# 16_PM8916_SMPS.net
KiCad netlist of a schematic drawn in Altium Designer
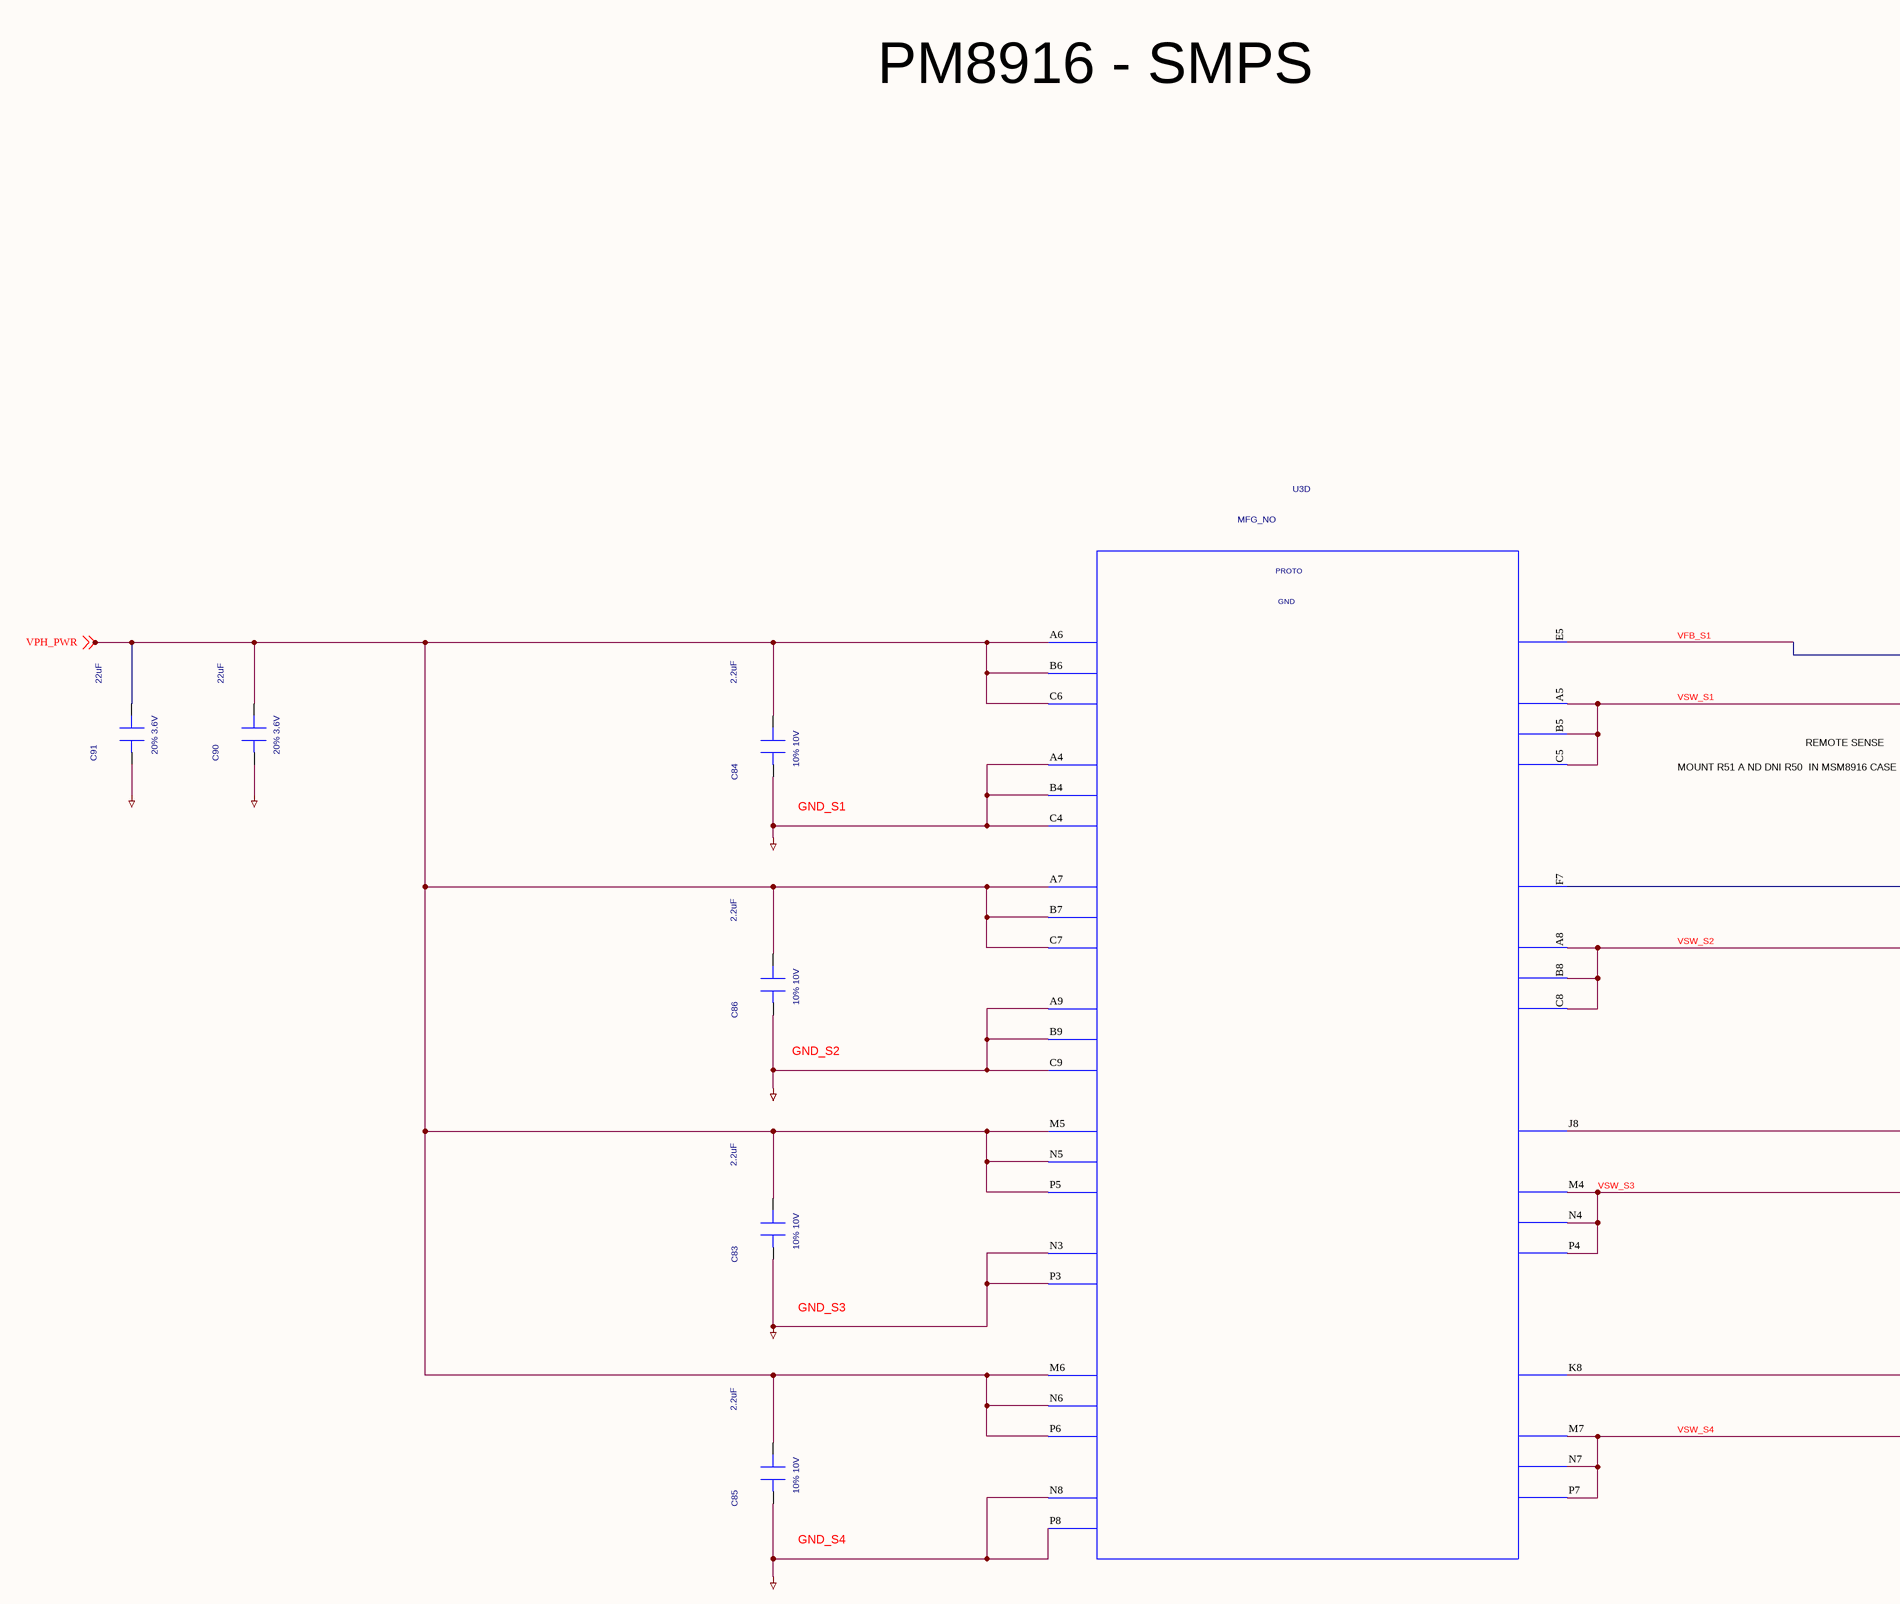
[diagram p0: 16 PM8916_SMPS.SchDoc, top left]
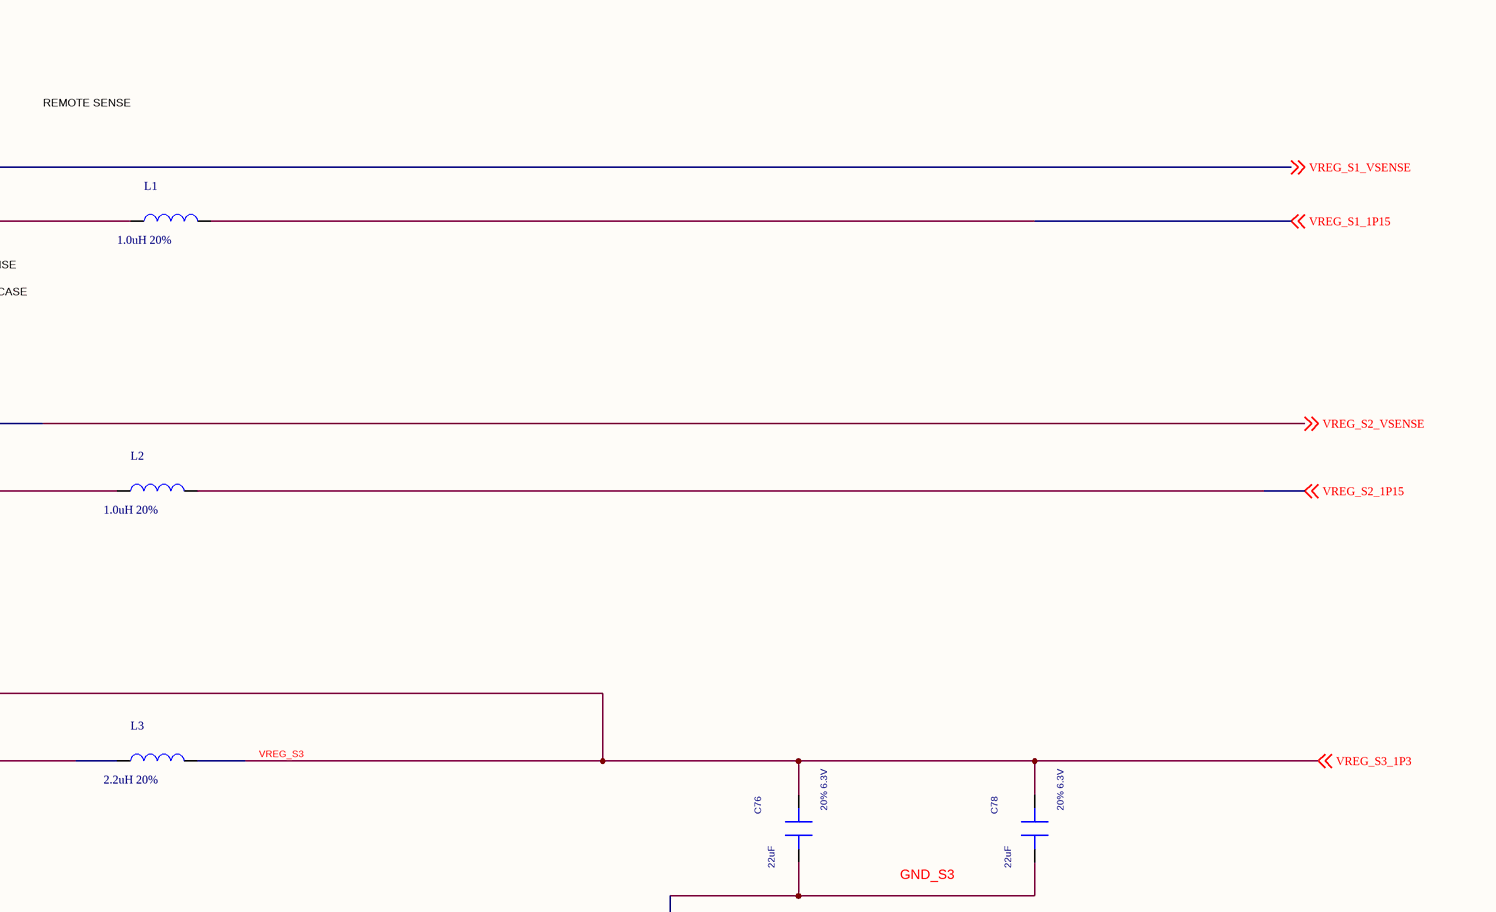
[diagram p1: 16 PM8916_SMPS.SchDoc, top right]
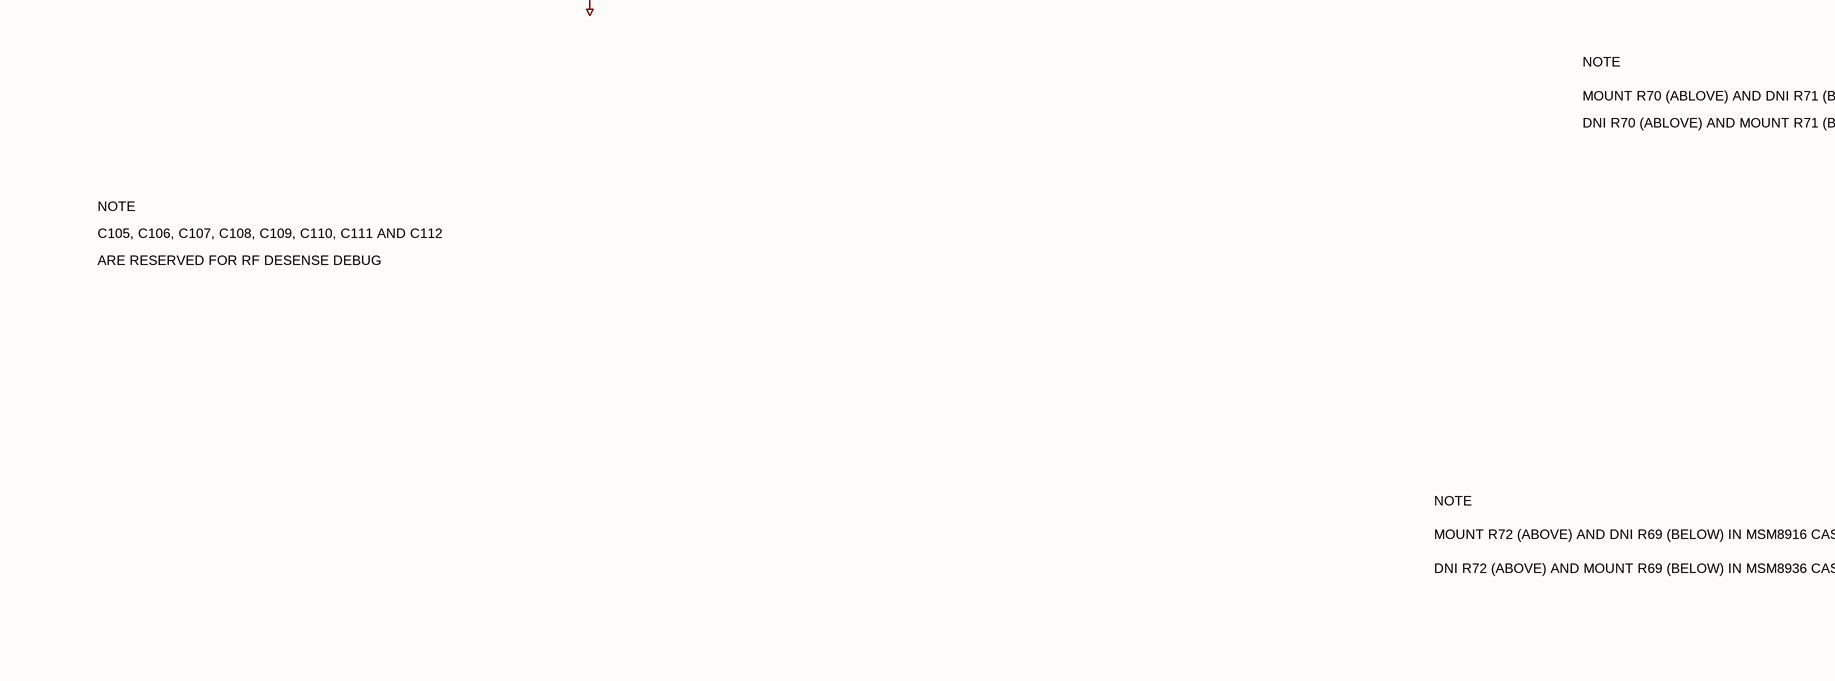
[diagram p2: 16 PM8916_SMPS.SchDoc, bottom left]
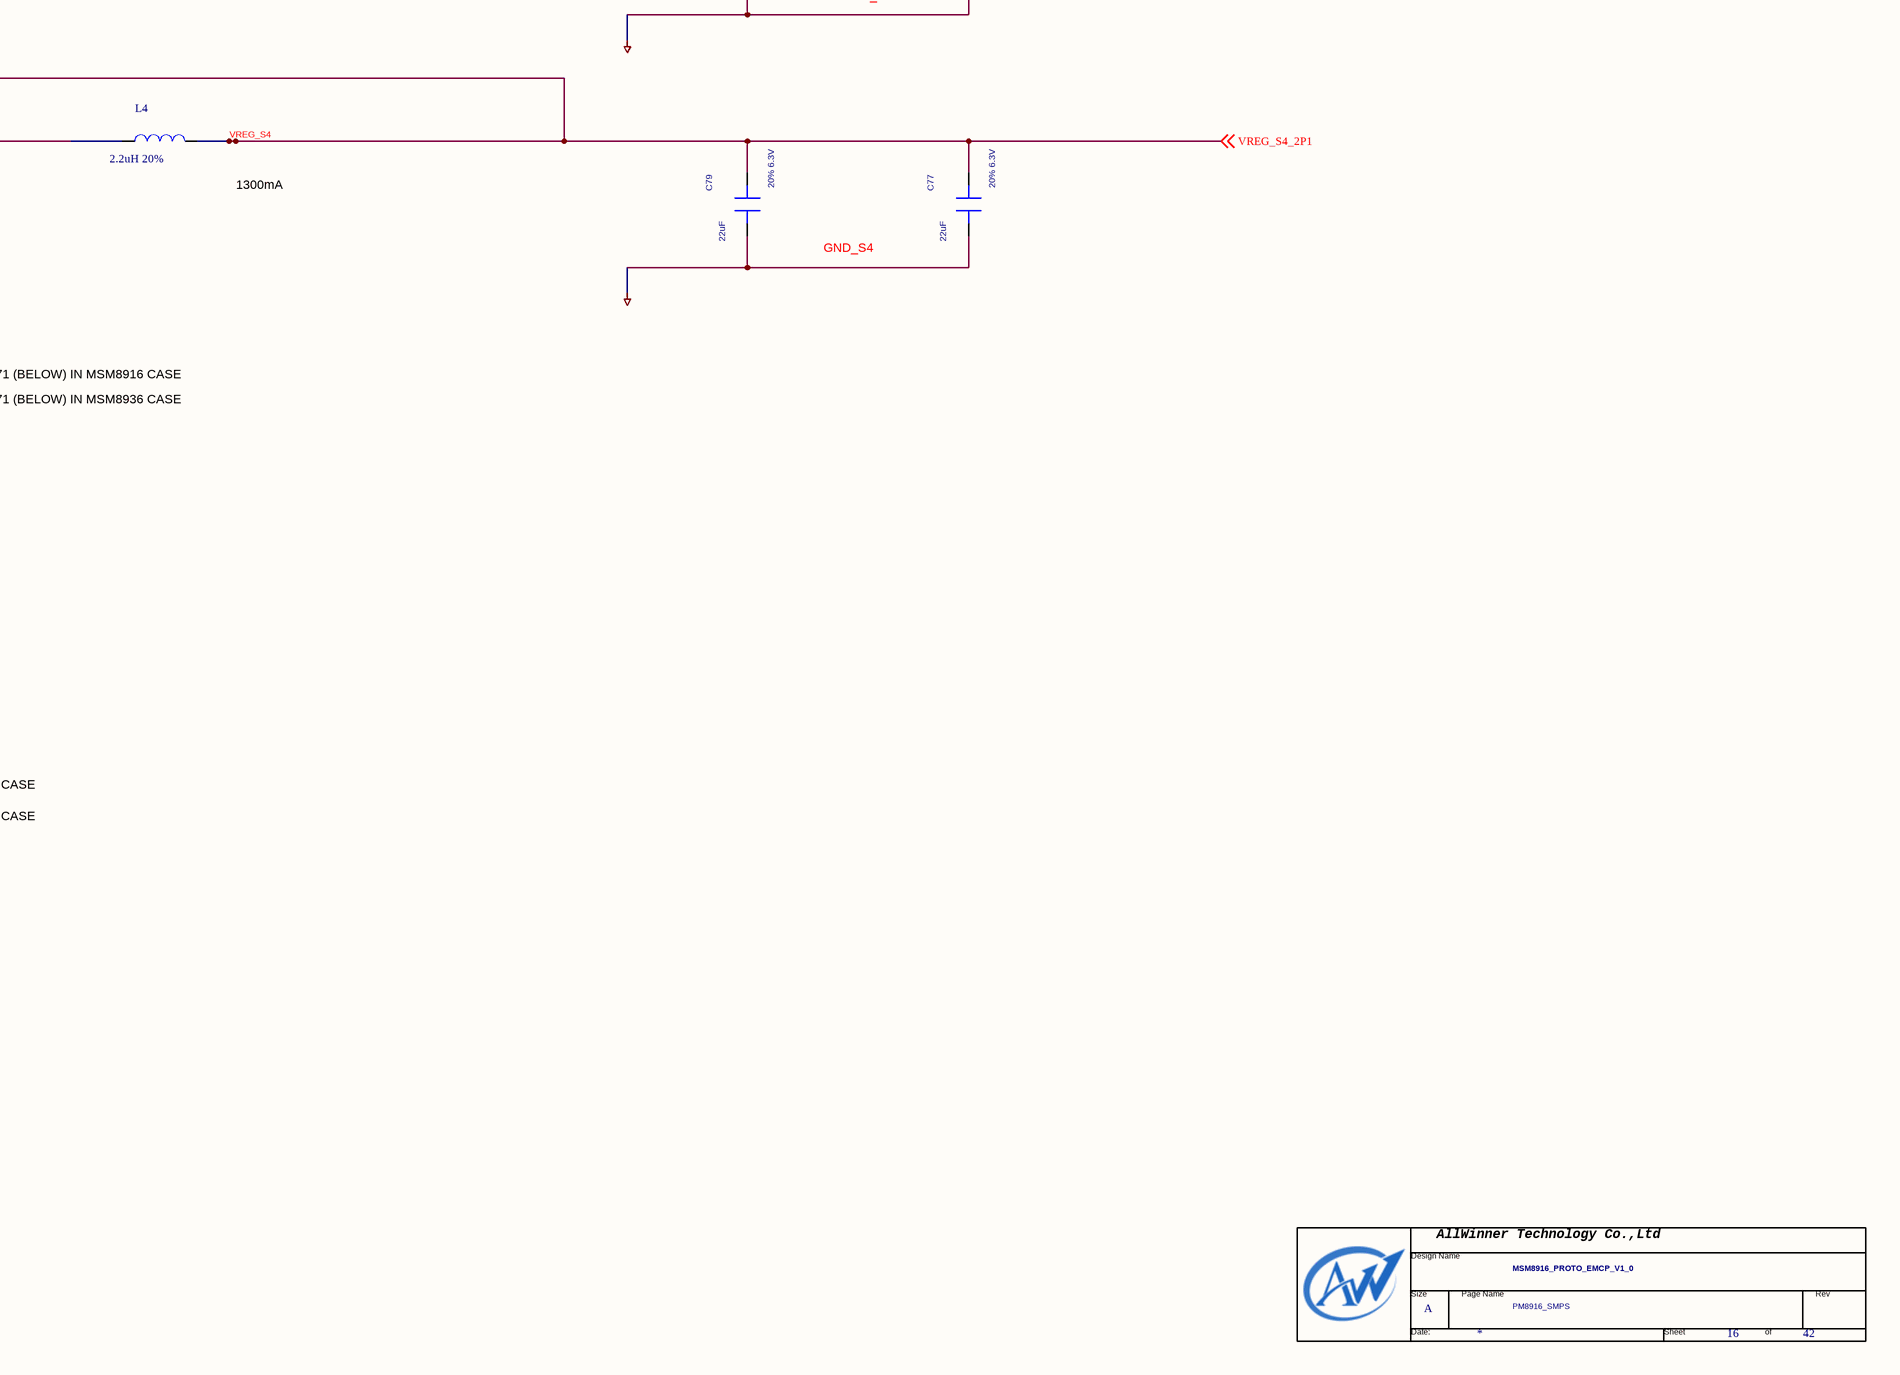
[diagram p3: 16 PM8916_SMPS.SchDoc, bottom right]

(export (version "E")
  (design (tool "Eeschema 10.0.6"))
  (components
    (comp (ref "C76")
      (value "22uF")
      (footprint "c0402")
      (fields (field (name "TOLERANCE") "20% 6.3V") (field (name "PART_NUMBER") "MCN_NO"))
      (libsource (lib "MSM8916_DRAM_PMIC_REF_Library") (part "CAP#1"))
    )
    (comp (ref "C77")
      (value "22uF")
      (footprint "c0402")
      (fields (field (name "TOLERANCE") "20% 6.3V") (field (name "PART_NUMBER") "MCN_NO"))
      (libsource (lib "MSM8916_DRAM_PMIC_REF_Library") (part "CAP#1"))
    )
    (comp (ref "C78")
      (value "22uF")
      (footprint "c0402")
      (fields (field (name "TOLERANCE") "20% 6.3V") (field (name "PART_NUMBER") "MCN_NO"))
      (libsource (lib "MSM8916_DRAM_PMIC_REF_Library") (part "CAP#1"))
    )
    (comp (ref "C79")
      (value "22uF")
      (footprint "c0402")
      (fields (field (name "TOLERANCE") "20% 6.3V") (field (name "PART_NUMBER") "MCN_NO"))
      (libsource (lib "MSM8916_DRAM_PMIC_REF_Library") (part "CAP#1"))
    )
    (comp (ref "C83")
      (value "2.2uF")
      (footprint "c0402")
      (fields (field (name "TOLERANCE") "10% 10V") (field (name "PART_NUMBER") "MCN_NO"))
      (libsource (lib "MSM8916_DRAM_PMIC_REF_Library") (part "CAP#1"))
    )
    (comp (ref "C84")
      (value "2.2uF")
      (footprint "c0402")
      (fields (field (name "TOLERANCE") "10% 10V") (field (name "PART_NUMBER") "MCN_NO"))
      (libsource (lib "MSM8916_DRAM_PMIC_REF_Library") (part "CAP#1"))
    )
    (comp (ref "C85")
      (value "2.2uF")
      (footprint "c0402")
      (fields (field (name "TOLERANCE") "10% 10V") (field (name "PART_NUMBER") "MCN_NO"))
      (libsource (lib "MSM8916_DRAM_PMIC_REF_Library") (part "CAP#1"))
    )
    (comp (ref "C86")
      (value "2.2uF")
      (footprint "c0402")
      (fields (field (name "TOLERANCE") "10% 10V") (field (name "PART_NUMBER") "MCN_NO"))
      (libsource (lib "MSM8916_DRAM_PMIC_REF_Library") (part "CAP#1"))
    )
    (comp (ref "C90")
      (value "22uF")
      (footprint "c0402")
      (fields (field (name "TOLERANCE") "20% 3.6V") (field (name "PART_NUMBER") "MCN_NO"))
      (libsource (lib "MSM8916_DRAM_PMIC_REF_Library") (part "CAP#1"))
    )
    (comp (ref "C91")
      (value "22uF")
      (footprint "c0402")
      (fields (field (name "TOLERANCE") "20% 3.6V") (field (name "PART_NUMBER") "MCN_NO"))
      (libsource (lib "MSM8916_DRAM_PMIC_REF_Library") (part "CAP#1"))
    )
    (comp (ref "L1")
      (value "1.0uH 20%")
      (footprint "c0402")
      (libsource (lib "MSM8916_DRAM_PMIC_REF_Library") (part "INDUCTOR_0"))
    )
    (comp (ref "L2")
      (value "1.0uH 20%")
      (footprint "c0402")
      (libsource (lib "MSM8916_DRAM_PMIC_REF_Library") (part "INDUCTOR_0"))
    )
    (comp (ref "L3")
      (value "2.2uH 20%")
      (footprint "c0402")
      (libsource (lib "MSM8916_DRAM_PMIC_REF_Library") (part "INDUCTOR_0"))
    )
    (comp (ref "L4")
      (value "2.2uH 20%")
      (footprint "c0402")
      (libsource (lib "MSM8916_DRAM_PMIC_REF_Library") (part "INDUCTOR_0"))
    )
    (comp (ref "U3")
      (value "ASIC_PM8916")
      (footprint "PM-8916-0-176NSP-TR-00-0")
      (fields
        (field (name "SYMNAME") "GND")
        (field (name "PART_NUMBER") "MCN_NO")
        (field (name "PART_ID") "MFG_NO")
        (field (name "BLOCKID") "PROTO")
      )
      (libsource (lib "MSM8916_DRAM_PMIC_REF_Library") (part "ASIC_PM8916"))
    )
  )
  (nets
    (net (code "1") (name "/VSW_S1") (class "Default")
      (node (ref "L1") (pin "1") (pinfunction "1_1") (pintype "passive"))
      (node (ref "U3") (pin "A5") (pinfunction "VSW_S1_1_A5") (pintype "bidirectional"))
      (node (ref "U3") (pin "B5") (pinfunction "VSW_S1_2_B5") (pintype "bidirectional"))
      (node (ref "U3") (pin "C5") (pinfunction "VSW_S1_3_C5") (pintype "bidirectional"))
    )
    (net (code "2") (name "/VSW_S2") (class "Default")
      (node (ref "L2") (pin "1") (pinfunction "1_1") (pintype "passive"))
      (node (ref "U3") (pin "A8") (pinfunction "VSW_S2_1_A8") (pintype "bidirectional"))
      (node (ref "U3") (pin "B8") (pinfunction "VSW_S2_2_B8") (pintype "bidirectional"))
      (node (ref "U3") (pin "C8") (pinfunction "VSW_S2_3_C8") (pintype "bidirectional"))
    )
    (net (code "3") (name "/VSW_S3") (class "Default")
      (node (ref "L3") (pin "1") (pinfunction "1_1") (pintype "passive"))
      (node (ref "U3") (pin "M4") (pinfunction "VSW_S3_1_M4") (pintype "bidirectional"))
      (node (ref "U3") (pin "N4") (pinfunction "VSW_S3_2_N4") (pintype "bidirectional"))
      (node (ref "U3") (pin "P4") (pinfunction "VSW_S3_3_P4") (pintype "bidirectional"))
    )
    (net (code "4") (name "/VSW_S4") (class "Default")
      (node (ref "L4") (pin "1") (pinfunction "1_1") (pintype "passive"))
      (node (ref "U3") (pin "M7") (pinfunction "VSW_S4_1_M7") (pintype "bidirectional"))
      (node (ref "U3") (pin "N7") (pinfunction "VSW_S4_2_N7") (pintype "bidirectional"))
      (node (ref "U3") (pin "P7") (pinfunction "VSW_S4_3_P7") (pintype "bidirectional"))
    )
    (net (code "5") (name "DGND") (class "Default")
      (node (ref "C76") (pin "1") (pinfunction "POS_1") (pintype "bidirectional"))
      (node (ref "C77") (pin "1") (pinfunction "POS_1") (pintype "bidirectional"))
      (node (ref "C78") (pin "1") (pinfunction "POS_1") (pintype "bidirectional"))
      (node (ref "C79") (pin "1") (pinfunction "POS_1") (pintype "bidirectional"))
      (node (ref "C83") (pin "1") (pinfunction "POS_1") (pintype "bidirectional"))
      (node (ref "C84") (pin "1") (pinfunction "POS_1") (pintype "bidirectional"))
      (node (ref "C85") (pin "1") (pinfunction "POS_1") (pintype "bidirectional"))
      (node (ref "C86") (pin "1") (pinfunction "POS_1") (pintype "bidirectional"))
      (node (ref "C90") (pin "1") (pinfunction "POS_1") (pintype "bidirectional"))
      (node (ref "C91") (pin "1") (pinfunction "POS_1") (pintype "bidirectional"))
      (node (ref "U3") (pin "A4") (pinfunction "GND_S1_1_A4") (pintype "input"))
      (node (ref "U3") (pin "A9") (pinfunction "GND_S2_1_A9") (pintype "input"))
      (node (ref "U3") (pin "B4") (pinfunction "GND_S1_2_B4") (pintype "input"))
      (node (ref "U3") (pin "B9") (pinfunction "GND_S2_2_B9") (pintype "input"))
      (node (ref "U3") (pin "C4") (pinfunction "GND_S1_3_C4") (pintype "input"))
      (node (ref "U3") (pin "C9") (pinfunction "GND_S2_3_C9") (pintype "input"))
      (node (ref "U3") (pin "N3") (pinfunction "GND_S3_1_N3") (pintype "input"))
      (node (ref "U3") (pin "N8") (pinfunction "GND_S4_1_N8") (pintype "input"))
      (node (ref "U3") (pin "P3") (pinfunction "GND_S3_2_P3") (pintype "input"))
      (node (ref "U3") (pin "P8") (pinfunction "GND_S4_2_P8") (pintype "input"))
    )
    (net (code "6") (name "VPH_PWR") (class "Default")
      (node (ref "C83") (pin "2") (pinfunction "NEG_2") (pintype "bidirectional"))
      (node (ref "C84") (pin "2") (pinfunction "NEG_2") (pintype "bidirectional"))
      (node (ref "C85") (pin "2") (pinfunction "NEG_2") (pintype "bidirectional"))
      (node (ref "C86") (pin "2") (pinfunction "NEG_2") (pintype "bidirectional"))
      (node (ref "C90") (pin "2") (pinfunction "NEG_2") (pintype "bidirectional"))
      (node (ref "C91") (pin "2") (pinfunction "NEG_2") (pintype "bidirectional"))
      (node (ref "U3") (pin "A6") (pinfunction "VIN_S1_1_A6") (pintype "bidirectional"))
      (node (ref "U3") (pin "A7") (pinfunction "VIN_S2_1_A7") (pintype "bidirectional"))
      (node (ref "U3") (pin "B6") (pinfunction "VIN_S1_2_B6") (pintype "bidirectional"))
      (node (ref "U3") (pin "B7") (pinfunction "VIN_S2_2_B7") (pintype "bidirectional"))
      (node (ref "U3") (pin "C6") (pinfunction "VIN_S1_3_C6") (pintype "bidirectional"))
      (node (ref "U3") (pin "C7") (pinfunction "VIN_S2_3_C7") (pintype "bidirectional"))
      (node (ref "U3") (pin "M5") (pinfunction "VIN_S3_1_M5") (pintype "bidirectional"))
      (node (ref "U3") (pin "M6") (pinfunction "VIN_S4_1_M6") (pintype "bidirectional"))
      (node (ref "U3") (pin "N5") (pinfunction "VIN_S3_2_N5") (pintype "bidirectional"))
      (node (ref "U3") (pin "N6") (pinfunction "VIN_S4_2_N6") (pintype "bidirectional"))
      (node (ref "U3") (pin "P5") (pinfunction "VIN_S3_3_P5") (pintype "bidirectional"))
      (node (ref "U3") (pin "P6") (pinfunction "VIN_S4_3_P6") (pintype "bidirectional"))
    )
    (net (code "7") (name "VREG_S1_1P15") (class "Default")
      (node (ref "L1") (pin "2") (pinfunction "2_2") (pintype "passive"))
    )
    (net (code "8") (name "VREG_S1_VSENSE") (class "Default")
      (node (ref "U3") (pin "E5") (pinfunction "VFB_S1_E5") (pintype "bidirectional"))
    )
    (net (code "9") (name "VREG_S2_1P15") (class "Default")
      (node (ref "L2") (pin "2") (pinfunction "2_2") (pintype "passive"))
    )
    (net (code "10") (name "VREG_S2_VSENSE") (class "Default")
      (node (ref "U3") (pin "F7") (pinfunction "VFB_S2_F7") (pintype "bidirectional"))
    )
    (net (code "11") (name "VREG_S3_1P3") (class "Default")
      (node (ref "C76") (pin "2") (pinfunction "NEG_2") (pintype "bidirectional"))
      (node (ref "C78") (pin "2") (pinfunction "NEG_2") (pintype "bidirectional"))
      (node (ref "L3") (pin "2") (pinfunction "2_2") (pintype "passive"))
      (node (ref "U3") (pin "J8") (pinfunction "VFB_S3_J8") (pintype "bidirectional"))
    )
    (net (code "12") (name "VREG_S4_2P1") (class "Default")
      (node (ref "C77") (pin "2") (pinfunction "NEG_2") (pintype "bidirectional"))
      (node (ref "C79") (pin "2") (pinfunction "NEG_2") (pintype "bidirectional"))
      (node (ref "L4") (pin "2") (pinfunction "2_2") (pintype "passive"))
      (node (ref "U3") (pin "K8") (pinfunction "VFB_S4_K8") (pintype "bidirectional"))
    )
  )
)
